# VREG.net
KiCad netlist of a schematic drawn in Altium Designer
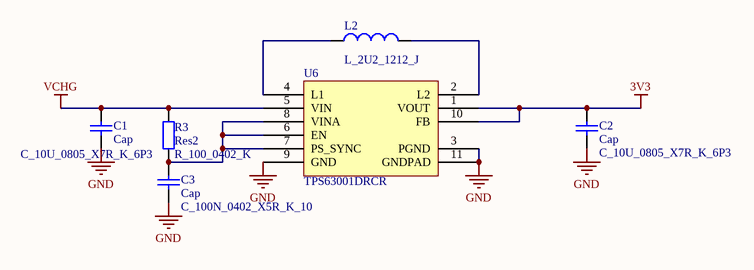
[diagram p0: VREG.SchDoc]

(export (version "E")
  (design (tool "Eeschema 10.0.6"))
  (components
    (comp (ref "C1")
      (value "Cap")
      (footprint "C_0805")
      (description "Capacitor")
      (fields
        (field (name "ALTIUM_VALUE") "C_10U_0805_X7R_K_6P3")
        (field (name "PUBLISHER") "Altium Limited")
      )
      (libsource (lib "Miscellaneous Devices") (part "Cap"))
    )
    (comp (ref "C2")
      (value "Cap")
      (footprint "C_0805")
      (description "Capacitor")
      (fields
        (field (name "ALTIUM_VALUE") "C_10U_0805_X7R_K_6P3")
        (field (name "PUBLISHER") "Altium Limited")
      )
      (libsource (lib "Miscellaneous Devices") (part "Cap"))
    )
    (comp (ref "C3")
      (value "Cap")
      (footprint "C_0402")
      (description "Capacitor")
      (fields
        (field (name "ALTIUM_VALUE") "C_100N_0402_X5R_K_10")
        (field (name "PUBLISHER") "Altium Limited")
      )
      (libsource (lib "Miscellaneous Devices") (part "Cap"))
    )
    (comp (ref "L2")
      (value "L_2U2_1212_J")
      (footprint "L_1212")
      (description "Inductor")
      (fields (field (name "PUBLISHER") "Altium Limited"))
      (libsource (lib "Miscellaneous Devices") (part "Inductor"))
    )
    (comp (ref "R3")
      (value "Res2")
      (footprint "R_0402")
      (description "Resistor")
      (fields (field (name "ALTIUM_VALUE") "R_100_0402_K") (field (name "PUBLISHER") "Altium Limited"))
      (libsource (lib "Miscellaneous Devices") (part "Res2"))
    )
    (comp (ref "U6")
      (value "TPS63001DRCR")
      (footprint "S-PVSON-N10")
      (description "DC/DC Switching Regulators 96% Buck-Boost Conv")
      (fields (field (name "MANUFACTURER") "Texas Instruments"))
      (libsource (lib "BrewBit") (part "TPS63001DRCR"))
    )
  )
  (nets
    (net (code "1") (name "3V3") (class "Default")
      (node (ref "C2") (pin "2") (pinfunction "2_2") (pintype "passive"))
      (node (ref "U6") (pin "1") (pinfunction "VOUT_1") (pintype "passive"))
      (node (ref "U6") (pin "10") (pinfunction "FB_10") (pintype "passive"))
    )
    (net (code "2") (name "GND") (class "Default")
      (node (ref "C1") (pin "1") (pinfunction "1_1") (pintype "passive"))
      (node (ref "C2") (pin "1") (pinfunction "1_1") (pintype "passive"))
      (node (ref "C3") (pin "1") (pinfunction "1_1") (pintype "passive"))
      (node (ref "U6") (pin "11") (pinfunction "GNDPAD_11") (pintype "passive"))
      (node (ref "U6") (pin "3") (pinfunction "PGND_3") (pintype "passive"))
      (node (ref "U6") (pin "9") (pinfunction "GND_9") (pintype "passive"))
    )
    (net (code "3") (name "Net-(U6-EN)") (class "Default")
      (node (ref "C3") (pin "2") (pinfunction "2_2") (pintype "passive"))
      (node (ref "R3") (pin "1") (pinfunction "1_1") (pintype "passive"))
      (node (ref "U6") (pin "6") (pinfunction "EN_6") (pintype "passive"))
      (node (ref "U6") (pin "7") (pinfunction "PS_SYNC_7") (pintype "passive"))
      (node (ref "U6") (pin "8") (pinfunction "VINA_8") (pintype "passive"))
    )
    (net (code "4") (name "Net-(U6-L1)") (class "Default")
      (node (ref "L2") (pin "1") (pinfunction "1_1") (pintype "passive"))
      (node (ref "U6") (pin "4") (pinfunction "L1_4") (pintype "passive"))
    )
    (net (code "5") (name "Net-(U6-L2)") (class "Default")
      (node (ref "L2") (pin "2") (pinfunction "2_2") (pintype "passive"))
      (node (ref "U6") (pin "2") (pinfunction "L2_2") (pintype "passive"))
    )
    (net (code "6") (name "VCHG") (class "Default")
      (node (ref "C1") (pin "2") (pinfunction "2_2") (pintype "passive"))
      (node (ref "R3") (pin "2") (pinfunction "2_2") (pintype "passive"))
      (node (ref "U6") (pin "5") (pinfunction "VIN_5") (pintype "passive"))
    )
  )
)
